# SV601272A-Current-Control.net
KiCad netlist of a schematic drawn in Altium Designer
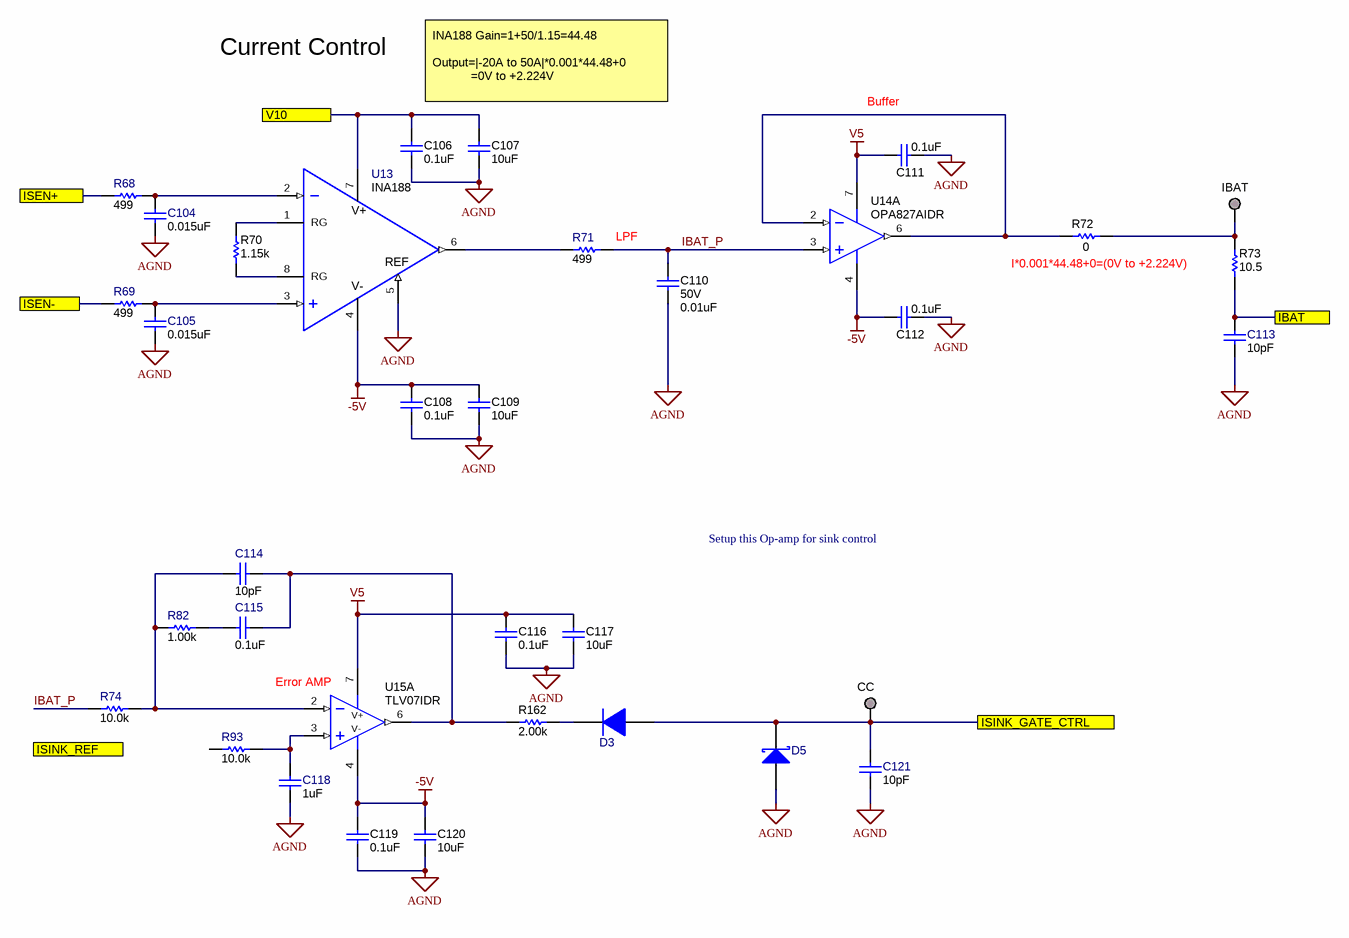
[diagram p0: SV601272A-Current-Control.SchDoc]

(export (version "E")
  (design (tool "Eeschema 10.0.6"))
  (components
    (comp (ref "C104")
      (value "Capacitor")
      (footprint "0603")
      (description "CAP, CERM, 0.015 uF, 16 V, +/- 10%, X7R, 0603")
      (fields
        (field (name "PARTNUMBER") "GRM188R71C153KA01D")
        (field (name "VALUEDISPLAYED") "0.015uF")
        (field (name "MANUFACTURER") "MuRata")
        (field (name "PUBLISHER") "Texas Instruments")
      )
      (libsource (lib "Altium Vault - TI") (part "CMP-0007383-5"))
    )
    (comp (ref "C105")
      (value "Capacitor")
      (footprint "0603")
      (description "CAP, CERM, 0.015 uF, 16 V, +/- 10%, X7R, 0603")
      (fields
        (field (name "PARTNUMBER") "GRM188R71C153KA01D")
        (field (name "VALUEDISPLAYED") "0.015uF")
        (field (name "MANUFACTURER") "MuRata")
        (field (name "PUBLISHER") "Texas Instruments")
      )
      (libsource (lib "Altium Vault - TI") (part "CMP-0007383-5"))
    )
    (comp (ref "C106")
      (value "Capacitor")
      (footprint "0603")
      (description "CAP, CERM, 0.1 uF, 25 V, +/- 5%, X7R, 0603")
      (fields
        (field (name "PARTNUMBER") "06033C104JAT2A")
        (field (name "VALUEDISPLAYED") "0.1uF")
        (field (name "MANUFACTURER") "AVX")
        (field (name "PUBLISHER") "Texas Instruments")
      )
      (libsource (lib "Altium Vault - TI") (part "CMP-0006752-5"))
    )
    (comp (ref "C107")
      (value "Capacitor")
      (footprint "0805_HV")
      (description "CAP, CERM, 10 uF, 10 V, +/- 10%, X7R, 0805")
      (fields
        (field (name "PARTNUMBER") "GRM21BR71A106KE51L")
        (field (name "VALUEDISPLAYED") "10uF")
        (field (name "MANUFACTURER") "MuRata")
        (field (name "PUBLISHER") "Texas Instruments")
      )
      (libsource (lib "Altium Vault - TI") (part "CMP-0008315-2"))
    )
    (comp (ref "C108")
      (value "Capacitor")
      (footprint "0603")
      (description "CAP, CERM, 0.1 uF, 25 V, +/- 5%, X7R, 0603")
      (fields
        (field (name "PARTNUMBER") "06033C104JAT2A")
        (field (name "VALUEDISPLAYED") "0.1uF")
        (field (name "MANUFACTURER") "AVX")
        (field (name "PUBLISHER") "Texas Instruments")
      )
      (libsource (lib "Altium Vault - TI") (part "CMP-0006752-5"))
    )
    (comp (ref "C109")
      (value "Capacitor")
      (footprint "0805_HV")
      (description "CAP, CERM, 10 uF, 10 V, +/- 10%, X7R, 0805")
      (fields
        (field (name "PARTNUMBER") "GRM21BR71A106KE51L")
        (field (name "VALUEDISPLAYED") "10uF")
        (field (name "MANUFACTURER") "MuRata")
        (field (name "PUBLISHER") "Texas Instruments")
      )
      (libsource (lib "Altium Vault - TI") (part "CMP-0008315-2"))
    )
    (comp (ref "C110")
      (value "GCM188R71H103KA37D")
      (footprint "0603")
      (description "CAP, CERM, 0.01 uF, 50 V, +/- 10%, X7R, AEC-Q200 Grade 1, 0603")
      (fields
        (field (name "MANUFACTURER") "MuRata")
        (field (name "VDC_V") "50V")
        (field (name "VALUEDISPLAYED") "0.01uF")
        (field (name "PUBLISHER") "Texas Instruments")
      )
      (libsource (lib "Altium Vault - TI") (part "CMP-0007143-4"))
    )
    (comp (ref "C111")
      (value "Capacitor")
      (footprint "0603")
      (description "CAP, CERM, 0.1 uF, 25 V, +/- 5%, X7R, 0603")
      (fields
        (field (name "PARTNUMBER") "06033C104JAT2A")
        (field (name "VALUEDISPLAYED") "0.1uF")
        (field (name "MANUFACTURER") "AVX")
        (field (name "PUBLISHER") "Texas Instruments")
      )
      (libsource (lib "Altium Vault - TI") (part "CMP-0006752-5"))
    )
    (comp (ref "C112")
      (value "Capacitor")
      (footprint "0603")
      (description "CAP, CERM, 0.1 uF, 25 V, +/- 5%, X7R, 0603")
      (fields
        (field (name "PARTNUMBER") "06033C104JAT2A")
        (field (name "VALUEDISPLAYED") "0.1uF")
        (field (name "MANUFACTURER") "AVX")
        (field (name "PUBLISHER") "Texas Instruments")
      )
      (libsource (lib "Altium Vault - TI") (part "CMP-0006752-5"))
    )
    (comp (ref "C113")
      (value "Capacitor")
      (footprint "0603")
      (description "CAP, CERM, 10 pF, 50 V, +/- 5%, C0G/NP0, 0603")
      (fields
        (field (name "PARTNUMBER") "GRM1885C1H100JA01D")
        (field (name "VALUEDISPLAYED") "10pF")
        (field (name "MANUFACTURER") "MuRata")
        (field (name "PUBLISHER") "Texas Instruments")
      )
      (libsource (lib "Altium Vault - TI") (part "CMP-0007170-4"))
    )
    (comp (ref "C114")
      (value "Capacitor")
      (footprint "0603")
      (description "CAP, CERM, 10 pF, 50 V, +/- 5%, C0G/NP0, 0603")
      (fields
        (field (name "PARTNUMBER") "GRM1885C1H100JA01D")
        (field (name "VALUEDISPLAYED") "10pF")
        (field (name "MANUFACTURER") "MuRata")
        (field (name "PUBLISHER") "Texas Instruments")
      )
      (libsource (lib "Altium Vault - TI") (part "CMP-0007170-4"))
    )
    (comp (ref "C115")
      (value "Capacitor")
      (footprint "0603")
      (description "CAP, CERM, 0.1 uF, 16 V, +/- 10%, X5R, 0603")
      (fields
        (field (name "PARTNUMBER") "GRM188R61C104KA01D")
        (field (name "VALUEDISPLAYED") "0.1uF")
        (field (name "MANUFACTURER") "MuRata")
        (field (name "PUBLISHER") "Texas Instruments")
      )
      (libsource (lib "Altium Vault - TI") (part "CMP-0007334-5"))
    )
    (comp (ref "C116")
      (value "Capacitor")
      (footprint "0603")
      (description "CAP, CERM, 0.1 uF, 25 V, +/- 5%, X7R, 0603")
      (fields
        (field (name "PARTNUMBER") "06033C104JAT2A")
        (field (name "VALUEDISPLAYED") "0.1uF")
        (field (name "MANUFACTURER") "AVX")
        (field (name "PUBLISHER") "Texas Instruments")
      )
      (libsource (lib "Altium Vault - TI") (part "CMP-0006752-5"))
    )
    (comp (ref "C117")
      (value "Capacitor")
      (footprint "0805_HV")
      (description "CAP, CERM, 10 uF, 10 V, +/- 10%, X7R, 0805")
      (fields
        (field (name "PARTNUMBER") "GRM21BR71A106KE51L")
        (field (name "VALUEDISPLAYED") "10uF")
        (field (name "MANUFACTURER") "MuRata")
        (field (name "PUBLISHER") "Texas Instruments")
      )
      (libsource (lib "Altium Vault - TI") (part "CMP-0008315-2"))
    )
    (comp (ref "C118")
      (value "Capacitor")
      (footprint "0603")
      (description "CAP, CERM, 1 uF, 6.3 V, +/- 10%, X5R, 0603")
      (fields
        (field (name "PARTNUMBER") "GRM188R60J105KA01D")
        (field (name "VALUEDISPLAYED") "1uF")
        (field (name "MANUFACTURER") "MuRata")
        (field (name "PUBLISHER") "Texas Instruments")
      )
      (libsource (lib "Altium Vault - TI") (part "CMP-0007302-5"))
    )
    (comp (ref "C119")
      (value "Capacitor")
      (footprint "0603")
      (description "CAP, CERM, 0.1 uF, 25 V, +/- 5%, X7R, 0603")
      (fields
        (field (name "PARTNUMBER") "06033C104JAT2A")
        (field (name "VALUEDISPLAYED") "0.1uF")
        (field (name "MANUFACTURER") "AVX")
        (field (name "PUBLISHER") "Texas Instruments")
      )
      (libsource (lib "Altium Vault - TI") (part "CMP-0006752-5"))
    )
    (comp (ref "C120")
      (value "Capacitor")
      (footprint "0805_HV")
      (description "CAP, CERM, 10 uF, 10 V, +/- 10%, X7R, 0805")
      (fields
        (field (name "PARTNUMBER") "GRM21BR71A106KE51L")
        (field (name "VALUEDISPLAYED") "10uF")
        (field (name "MANUFACTURER") "MuRata")
        (field (name "PUBLISHER") "Texas Instruments")
      )
      (libsource (lib "Altium Vault - TI") (part "CMP-0008315-2"))
    )
    (comp (ref "C121")
      (value "Capacitor")
      (footprint "0603")
      (description "CAP, CERM, 10 pF, 50 V, +/- 5%, C0G/NP0, 0603")
      (fields
        (field (name "PARTNUMBER") "GRM1885C1H100JA01D")
        (field (name "VALUEDISPLAYED") "10pF")
        (field (name "MANUFACTURER") "MuRata")
        (field (name "PUBLISHER") "Texas Instruments")
      )
      (libsource (lib "Altium Vault - TI") (part "CMP-0007170-4"))
    )
    (comp (ref "CC")
      (value "Pogo Pad")
      (footprint "PogoPad")
      (description "Pad for Pogo Pin Connector")
      (fields (field (name "SYMBOLCREATOR") "codlsc") (field (name "PUBLISHER") "Texas Instruments"))
      (libsource (lib "MiscParts") (part "PogoPad"))
    )
    (comp (ref "D3")
      (value "DIODE")
      (footprint "SOD-523")
      (description "Diode, Switching, 75 V, 0.3 A, SOD-523")
      (fields
        (field (name "PARTNUMBER") "1N4148X-TP")
        (field (name "MANUFACTURER") "Micro Commercial Components")
        (field (name "PUBLISHER") "Texas Instruments")
      )
      (libsource (lib "Altium Vault - TI") (part "CMP-0076957-2"))
    )
    (comp (ref "D5")
      (value "DIODE_SCHOTTKY")
      (footprint "SOD-323")
      (description "Diode, Schottky, 30 V, 0.2 A, SOD-323")
      (fields
        (field (name "PARTNUMBER") "BAT54WS-7-F")
        (field (name "MANUFACTURER") "Diodes Inc.")
        (field (name "PUBLISHER") "Texas Instruments")
      )
      (libsource (lib "Altium Vault - TI") (part "CMP-0028458-1"))
    )
    (comp (ref "IBAT")
      (value "Pogo Pad")
      (footprint "PogoPad")
      (description "Pad for Pogo Pin Connector")
      (fields (field (name "SYMBOLCREATOR") "codlsc") (field (name "PUBLISHER") "Texas Instruments"))
      (libsource (lib "MiscParts") (part "PogoPad"))
    )
    (comp (ref "R68")
      (value "Resistor")
      (footprint "0603")
      (description "RES, 499, 1%, 0.1 W, AEC-Q200 Grade 0, 0603")
      (fields
        (field (name "PARTNUMBER") "CRCW0603499RFKEA")
        (field (name "VALUEDISPLAYED") "499")
        (field (name "MANUFACTURER") "Vishay-Dale")
      )
      (libsource (lib "Altium Vault - TI") (part "CMP-0022446-5"))
    )
    (comp (ref "R69")
      (value "Resistor")
      (footprint "0603")
      (description "RES, 499, 1%, 0.1 W, AEC-Q200 Grade 0, 0603")
      (fields
        (field (name "PARTNUMBER") "CRCW0603499RFKEA")
        (field (name "VALUEDISPLAYED") "499")
        (field (name "MANUFACTURER") "Vishay-Dale")
      )
      (libsource (lib "Altium Vault - TI") (part "CMP-0022446-5"))
    )
    (comp (ref "R70")
      (value "1.15k")
      (footprint "0603")
      (description "RES, 1.15 k, 0.1%, 0.1 W, 0603")
      (fields
        (field (name "MANUFACTURER") "Yageo America")
        (field (name "PARTNUMBER") "RT0603BRD071K15L")
        (field (name "PUBLISHER") "Texas Instruments")
      )
      (libsource (lib "Altium Vault - TI") (part "CMP-0023872-3"))
    )
    (comp (ref "R71")
      (value "Resistor")
      (footprint "0603")
      (description "RES, 499, 1%, 0.1 W, AEC-Q200 Grade 0, 0603")
      (fields
        (field (name "PARTNUMBER") "CRCW0603499RFKEA")
        (field (name "VALUEDISPLAYED") "499")
        (field (name "MANUFACTURER") "Vishay-Dale")
      )
      (libsource (lib "Altium Vault - TI") (part "CMP-0022446-5"))
    )
    (comp (ref "R72")
      (value "Resistor")
      (footprint "0603")
      (description "RES, 0, 5%, 0.1 W, 0603")
      (fields
        (field (name "PARTNUMBER") "ERJ-3GEY0R00V")
        (field (name "MANUFACTURER") "Panasonic")
        (field (name "VALUEDISPLAYED") "0")
        (field (name "PUBLISHER") "Texas Instruments")
      )
      (libsource (lib "Altium Vault - TI") (part "CMP-0025874-3"))
    )
    (comp (ref "R73")
      (value "RC0603FR-0710R5L")
      (footprint "0603")
      (description "RES, 10.5, 1%, 0.1 W, 0603")
      (fields
        (field (name "MANUFACTURER") "Yageo America")
        (field (name "VALUEDISPLAYED") "10.5")
        (field (name "PUBLISHER") "Texas Instruments")
      )
      (libsource (lib "Altium Vault - TI") (part "CMP-0022749-2"))
    )
    (comp (ref "R74")
      (value "Resistor")
      (footprint "0603")
      (description "RES, 10.0 k, 1%, 0.1 W, 0603")
      (fields
        (field (name "PARTNUMBER") "RC0603FR-0710KL")
        (field (name "VALUEDISPLAYED") "10.0k")
        (field (name "MANUFACTURER") "Yageo America")
        (field (name "PUBLISHER") "Texas Instruments")
      )
      (libsource (lib "Altium Vault - TI") (part "CMP-0022746-3"))
    )
    (comp (ref "R82")
      (value "Resistor")
      (footprint "0603")
      (description "RES, 1.00 k, 1%, 0.1 W, 0603")
      (fields
        (field (name "PARTNUMBER") "RC0603FR-071KL")
        (field (name "VALUEDISPLAYED") "1.00k")
        (field (name "MANUFACTURER") "Yageo America")
        (field (name "PUBLISHER") "Texas Instruments")
      )
      (libsource (lib "Altium Vault - TI") (part "CMP-0022895-3"))
    )
    (comp (ref "R93")
      (value "Resistor")
      (footprint "0603")
      (description "RES, 10.0 k, 1%, 0.1 W, 0603")
      (fields
        (field (name "PARTNUMBER") "RC0603FR-0710KL")
        (field (name "VALUEDISPLAYED") "10.0k")
        (field (name "MANUFACTURER") "Yageo America")
        (field (name "PUBLISHER") "Texas Instruments")
      )
      (libsource (lib "Altium Vault - TI") (part "CMP-0022746-3"))
    )
    (comp (ref "R162")
      (value "RT0603DRE072KL")
      (footprint "0603")
      (description "RES, 2.00 k, 0.5%, 0.1 W, 0603")
      (fields
        (field (name "MANUFACTURER") "Yageo America")
        (field (name "VALUEDISPLAYED") "2.00k")
        (field (name "PUBLISHER") "Texas Instruments")
      )
      (libsource (lib "Altium Vault - TI") (part "CMP-0025080-3"))
    )
    (comp (ref "U13")
      (value "INA188")
      (footprint "D0008A_N")
      (description "36-V, Zero-Drift, Rail-to-Rail-Out Instrumentation Amplifier, D0008A (SOIC-8)")
      (fields
        (field (name "PARTNUMBER") "INA188IDR")
        (field (name "ALTERNATE PARTNUMBER") "INA188ID")
        (field (name "PUBLISHER") "Texas Instruments")
      )
      (libsource (lib "Altium Vault - TI") (part "CMP-0075744-1"))
    )
    (comp (ref "U14")
      (value "OPA827AIDR")
      (footprint "D0008A_L")
      (fields (field (name "MANUFACTURER") "Texas Instruments") (field (name "PARTNUMBER") "OPA827AIDR"))
      (libsource (lib "Altium Vault - TI") (part "CMP-0041267-2"))
    )
    (comp (ref "U15")
      (value "TLV07IDR")
      (footprint "D0008A_N")
      (description "36-V Precision, Rail-to-Rail Output, Operational Amplifier, D0008A (SOIC-8)")
      (fields (field (name "MANUFACTURER") "Texas Instruments") (field (name "PARTNUMBER") "TLV07IDR"))
      (libsource (lib "Altium Vault - TI") (part "CMP-0079847-1"))
    )
  )
  (nets
    (net (code "1") (name "-5V") (class "Default")
      (node (ref "C108") (pin "1") (pinfunction "1_1") (pintype "passive"))
      (node (ref "C109") (pin "1") (pinfunction "1_1") (pintype "passive"))
      (node (ref "C112") (pin "1") (pinfunction "1_1") (pintype "passive"))
      (node (ref "C119") (pin "1") (pinfunction "1_1") (pintype "passive"))
      (node (ref "C120") (pin "1") (pinfunction "1_1") (pintype "passive"))
      (node (ref "U13") (pin "4") (pinfunction "V-_4") (pintype "power_in"))
      (node (ref "U14") (pin "4") (pinfunction "V-_4") (pintype "power_in"))
      (node (ref "U15") (pin "4") (pinfunction "V-_4") (pintype "power_in"))
    )
    (net (code "2") (name "/IBAT") (class "Default")
      (node (ref "C113") (pin "2") (pinfunction "2_2") (pintype "passive"))
      (node (ref "R73") (pin "1") (pinfunction "1_1") (pintype "passive"))
    )
    (net (code "3") (name "/IBAT_P") (class "Default")
      (node (ref "C110") (pin "1") (pinfunction "1_1") (pintype "passive"))
      (node (ref "R71") (pin "1") (pinfunction "1_1") (pintype "passive"))
      (node (ref "R74") (pin "1") (pinfunction "1_1") (pintype "passive"))
      (node (ref "U14") (pin "3") (pinfunction "IN+_3") (pintype "input"))
    )
    (net (code "4") (name "/ISEN+") (class "Default")
      (node (ref "R68") (pin "2") (pinfunction "2_2") (pintype "passive"))
    )
    (net (code "5") (name "/ISEN-") (class "Default")
      (node (ref "R69") (pin "2") (pinfunction "2_2") (pintype "passive"))
    )
    (net (code "6") (name "/ISINK_GATE_CTRL") (class "Default")
      (node (ref "C121") (pin "2") (pinfunction "2_2") (pintype "passive"))
      (node (ref "CC") (pin "1") (pintype "passive"))
      (node (ref "D3") (pin "2") (pinfunction "A_2") (pintype "passive"))
      (node (ref "D5") (pin "1") (pinfunction "K_1") (pintype "passive"))
    )
    (net (code "8") (name "/V10") (class "Default")
      (node (ref "C106") (pin "1") (pinfunction "1_1") (pintype "passive"))
      (node (ref "C107") (pin "1") (pinfunction "1_1") (pintype "passive"))
      (node (ref "U13") (pin "7") (pinfunction "V+_7") (pintype "power_in"))
    )
    (net (code "9") (name "AGND") (class "Default")
      (node (ref "C104") (pin "2") (pinfunction "2_2") (pintype "passive"))
      (node (ref "C105") (pin "2") (pinfunction "2_2") (pintype "passive"))
      (node (ref "C106") (pin "2") (pinfunction "2_2") (pintype "passive"))
      (node (ref "C107") (pin "2") (pinfunction "2_2") (pintype "passive"))
      (node (ref "C108") (pin "2") (pinfunction "2_2") (pintype "passive"))
      (node (ref "C109") (pin "2") (pinfunction "2_2") (pintype "passive"))
      (node (ref "C110") (pin "2") (pinfunction "2_2") (pintype "passive"))
      (node (ref "C111") (pin "2") (pinfunction "2_2") (pintype "passive"))
      (node (ref "C112") (pin "2") (pinfunction "2_2") (pintype "passive"))
      (node (ref "C113") (pin "1") (pinfunction "1_1") (pintype "passive"))
      (node (ref "C116") (pin "2") (pinfunction "2_2") (pintype "passive"))
      (node (ref "C117") (pin "2") (pinfunction "2_2") (pintype "passive"))
      (node (ref "C118") (pin "1") (pinfunction "1_1") (pintype "passive"))
      (node (ref "C119") (pin "2") (pinfunction "2_2") (pintype "passive"))
      (node (ref "C120") (pin "2") (pinfunction "2_2") (pintype "passive"))
      (node (ref "C121") (pin "1") (pinfunction "1_1") (pintype "passive"))
      (node (ref "D5") (pin "2") (pinfunction "A_2") (pintype "passive"))
      (node (ref "U13") (pin "5") (pinfunction "REF_5") (pintype "input"))
    )
    (net (code "10") (name "Net-(C115-Pad2)") (class "Default")
      (node (ref "C115") (pin "2") (pinfunction "2_2") (pintype "passive"))
      (node (ref "R82") (pin "2") (pinfunction "2_2") (pintype "passive"))
    )
    (net (code "11") (name "Net-(D3-K)") (class "Default")
      (node (ref "D3") (pin "1") (pinfunction "K_1") (pintype "passive"))
      (node (ref "R162") (pin "2") (pinfunction "2_2") (pintype "passive"))
    )
    (net (code "12") (name "Net-(IBAT-Pad1)") (class "Default")
      (node (ref "IBAT") (pin "1") (pintype "passive"))
      (node (ref "R72") (pin "2") (pinfunction "2_2") (pintype "passive"))
      (node (ref "R73") (pin "2") (pinfunction "2_2") (pintype "passive"))
    )
    (net (code "13") (name "Net-(R70-Pad1)") (class "Default")
      (node (ref "R70") (pin "1") (pinfunction "1_1") (pintype "passive"))
      (node (ref "U13") (pin "8") (pinfunction "RG_8") (pintype "passive"))
    )
    (net (code "14") (name "Net-(R70-Pad2)") (class "Default")
      (node (ref "R70") (pin "2") (pinfunction "2_2") (pintype "passive"))
      (node (ref "U13") (pin "1") (pinfunction "RG_1") (pintype "passive"))
    )
    (net (code "15") (name "Net-(U13-IN+)") (class "Default")
      (node (ref "C105") (pin "1") (pinfunction "1_1") (pintype "passive"))
      (node (ref "R69") (pin "1") (pinfunction "1_1") (pintype "passive"))
      (node (ref "U13") (pin "3") (pinfunction "IN+_3") (pintype "input"))
    )
    (net (code "16") (name "Net-(U13-IN-)") (class "Default")
      (node (ref "C104") (pin "1") (pinfunction "1_1") (pintype "passive"))
      (node (ref "R68") (pin "1") (pinfunction "1_1") (pintype "passive"))
      (node (ref "U13") (pin "2") (pinfunction "IN-_2") (pintype "input"))
    )
    (net (code "17") (name "Net-(U13-OUT)") (class "Default")
      (node (ref "R71") (pin "2") (pinfunction "2_2") (pintype "passive"))
      (node (ref "U13") (pin "6") (pinfunction "OUT_6") (pintype "output"))
    )
    (net (code "18") (name "Net-(U14A-IN-)") (class "Default")
      (node (ref "R72") (pin "1") (pinfunction "1_1") (pintype "passive"))
      (node (ref "U14") (pin "2") (pinfunction "IN-_2") (pintype "input"))
      (node (ref "U14") (pin "6") (pinfunction "OUT_6") (pintype "output"))
    )
    (net (code "19") (name "Net-(U15A-IN+)") (class "Default")
      (node (ref "C118") (pin "2") (pinfunction "2_2") (pintype "passive"))
      (node (ref "R93") (pin "2") (pinfunction "2_2") (pintype "passive"))
      (node (ref "U15") (pin "3") (pinfunction "IN+_3") (pintype "input"))
    )
    (net (code "20") (name "Net-(U15A-IN-)") (class "Default")
      (node (ref "C114") (pin "1") (pinfunction "1_1") (pintype "passive"))
      (node (ref "R74") (pin "2") (pinfunction "2_2") (pintype "passive"))
      (node (ref "R82") (pin "1") (pinfunction "1_1") (pintype "passive"))
      (node (ref "U15") (pin "2") (pinfunction "IN-_2") (pintype "input"))
    )
    (net (code "21") (name "Net-(U15A-OUT)") (class "Default")
      (node (ref "C114") (pin "2") (pinfunction "2_2") (pintype "passive"))
      (node (ref "C115") (pin "1") (pinfunction "1_1") (pintype "passive"))
      (node (ref "R162") (pin "1") (pinfunction "1_1") (pintype "passive"))
      (node (ref "U15") (pin "6") (pinfunction "OUT_6") (pintype "output"))
    )
    (net (code "22") (name "V5") (class "Default")
      (node (ref "C111") (pin "1") (pinfunction "1_1") (pintype "passive"))
      (node (ref "C116") (pin "1") (pinfunction "1_1") (pintype "passive"))
      (node (ref "C117") (pin "1") (pinfunction "1_1") (pintype "passive"))
      (node (ref "U14") (pin "7") (pinfunction "V+_7") (pintype "power_in"))
      (node (ref "U15") (pin "7") (pinfunction "V+_7") (pintype "power_in"))
    )
    (net (code "23") (name "unconnected-(R93-Pad1)") (class "Default")
      (node (ref "R93") (pin "1") (pinfunction "1_1") (pintype "passive"))
    )
  )
)
